# BACKUP_POWER.net
KiCad netlist of a schematic drawn in Altium Designer
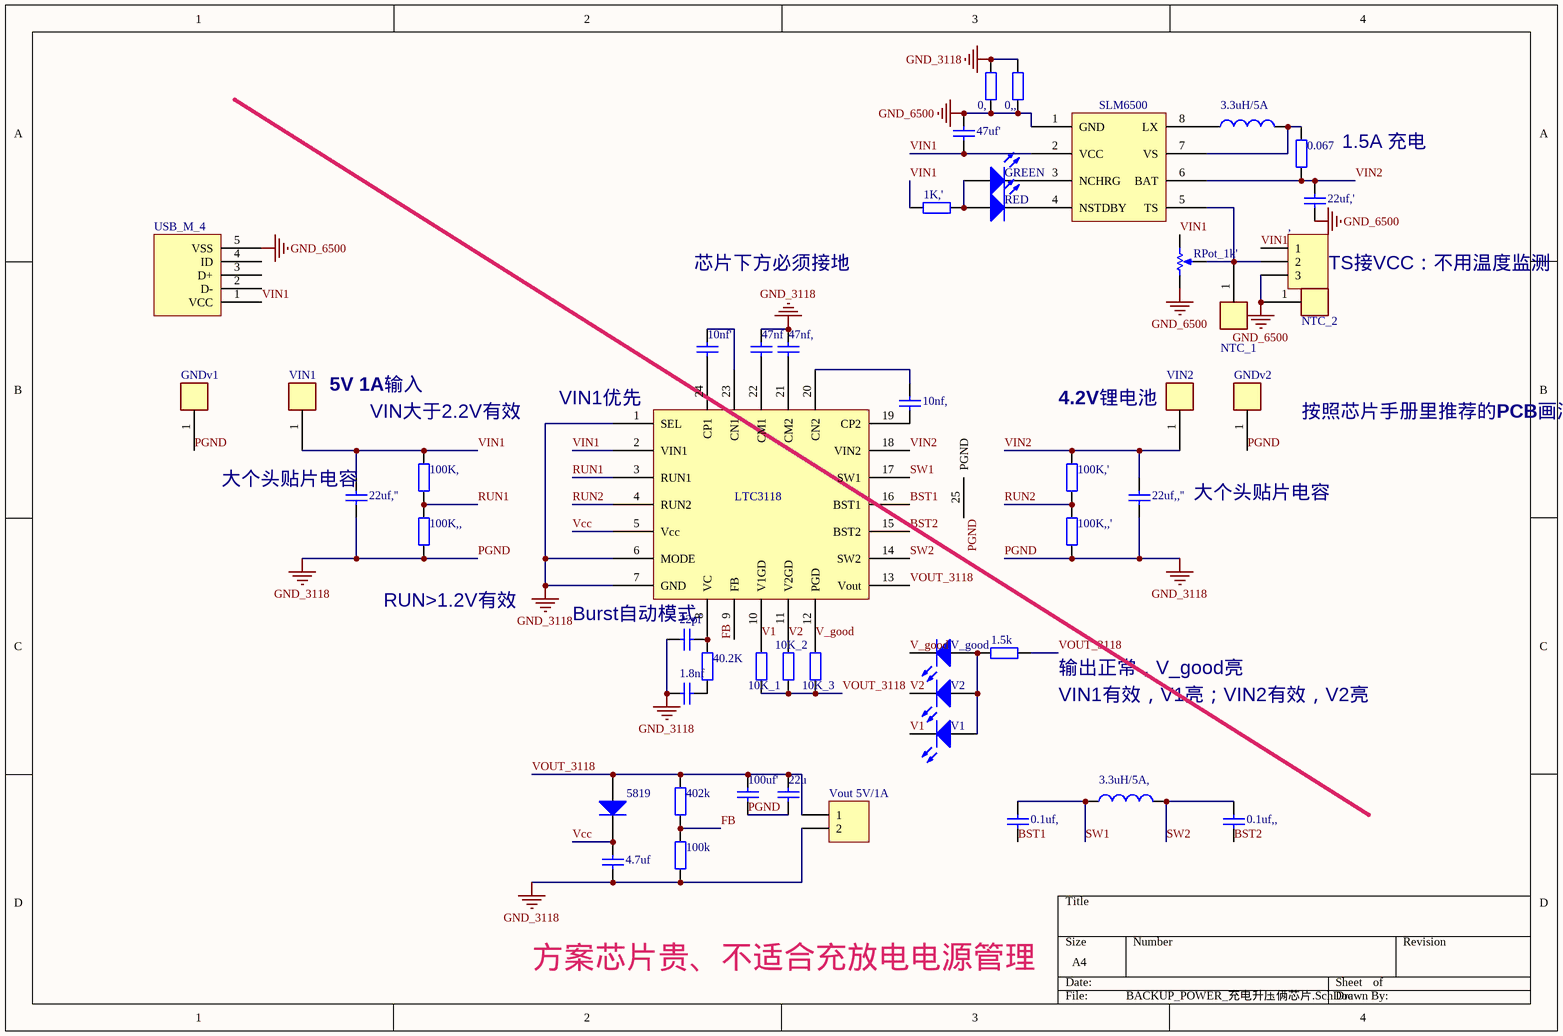
[diagram p0: BACKUP_POWER_充电升压俩芯片.SchDoc]

(export (version "E")
  (design (tool "Eeschema 10.0.6"))
  (components
    (comp (ref ",")
      (value "Header 3")
      (footprint "HDR1X3")
      (description "Header, 3-Pin")
      (fields (field (name "PUBLISHER") "Altium Limited"))
      (libsource (lib "Miscellaneous Connectors") (part "Header 3"))
    )
    (comp (ref "0,")
      (value "Res2")
      (footprint "0805A")
      (description "Resistor")
      (fields (field (name "PUBLISHER") "Altium Limited"))
      (libsource (lib "Miscellaneous Devices") (part "Res2"))
    )
    (comp (ref "0,,")
      (value "Res2")
      (footprint "0805A")
      (description "Resistor")
      (fields (field (name "PUBLISHER") "Altium Limited"))
      (libsource (lib "Miscellaneous Devices") (part "Res2"))
    )
    (comp (ref "0.1uf,")
      (value "Cap")
      (footprint "C-RAD-0805")
      (description "Capacitor")
      (fields (field (name "PUBLISHER") "Altium Limited"))
      (libsource (lib "Miscellaneous Devices") (part "Cap"))
    )
    (comp (ref "0.1uf,,")
      (value "Cap")
      (footprint "C-RAD-0805")
      (description "Capacitor")
      (fields (field (name "PUBLISHER") "Altium Limited"))
      (libsource (lib "Miscellaneous Devices") (part "Cap"))
    )
    (comp (ref "0.067")
      (value "Res2")
      (footprint "1206R")
      (description "Resistor")
      (fields (field (name "PUBLISHER") "Altium Limited"))
      (libsource (lib "Miscellaneous Devices") (part "Res2"))
    )
    (comp (ref "1.5k")
      (value "Res2")
      (footprint "0805A")
      (description "Resistor")
      (fields (field (name "PUBLISHER") "Altium Limited"))
      (libsource (lib "") (part "Res2_1"))
    )
    (comp (ref "1.8nf")
      (value "Cap")
      (footprint "C-RAD-0805")
      (description "Capacitor")
      (fields (field (name "PUBLISHER") "Altium Limited"))
      (libsource (lib "Miscellaneous Devices") (part "Cap"))
    )
    (comp (ref "1K,'")
      (value "Res2")
      (footprint "0805A")
      (description "Resistor")
      (fields (field (name "PUBLISHER") "Altium Limited"))
      (libsource (lib "") (part "Res2_2"))
    )
    (comp (ref "3.3uH/5A")
      (value "Inductor")
      (footprint "6 X 6-L")
      (fields (field (name "PUBLISHER") "Altium Limited"))
      (libsource (lib "Miscellaneous Devices") (part "Inductor"))
    )
    (comp (ref "3.3uH/5A,")
      (value "Inductor")
      (footprint "6 X 6-L")
      (fields (field (name "PUBLISHER") "Altium Limited"))
      (libsource (lib "Miscellaneous Devices") (part "Inductor"))
    )
    (comp (ref "4.7uf")
      (value "Cap")
      (footprint "C-RAD-0805")
      (description "Capacitor")
      (fields (field (name "PUBLISHER") "Altium Limited"))
      (libsource (lib "Miscellaneous Devices") (part "Cap"))
    )
    (comp (ref "10K_1")
      (value "Res2")
      (footprint "0805A")
      (description "Resistor")
      (fields (field (name "PUBLISHER") "Altium Limited"))
      (libsource (lib "Miscellaneous Devices") (part "Res2"))
    )
    (comp (ref "10K_2")
      (value "Res2")
      (footprint "0805A")
      (description "Resistor")
      (fields (field (name "PUBLISHER") "Altium Limited"))
      (libsource (lib "Miscellaneous Devices") (part "Res2"))
    )
    (comp (ref "10K_3")
      (value "Res2")
      (footprint "0805A")
      (description "Resistor")
      (fields (field (name "PUBLISHER") "Altium Limited"))
      (libsource (lib "Miscellaneous Devices") (part "Res2"))
    )
    (comp (ref "10nf'")
      (value "Cap")
      (footprint "C-RAD-0805")
      (description "Capacitor")
      (fields (field (name "PUBLISHER") "Altium Limited"))
      (libsource (lib "Miscellaneous Devices") (part "Cap"))
    )
    (comp (ref "10nf,")
      (value "Cap")
      (footprint "C-RAD-0805")
      (description "Capacitor")
      (fields (field (name "PUBLISHER") "Altium Limited"))
      (libsource (lib "Miscellaneous Devices") (part "Cap"))
    )
    (comp (ref "22pf")
      (value "Cap")
      (footprint "C-RAD-0805")
      (description "Capacitor")
      (fields (field (name "PUBLISHER") "Altium Limited"))
      (libsource (lib "Miscellaneous Devices") (part "Cap"))
    )
    (comp (ref "22u")
      (value "Cap")
      (footprint "MISCEPCB:1812")
      (description "Capacitor")
      (fields (field (name "PUBLISHER") "Altium Limited"))
      (libsource (lib "Miscellaneous Devices") (part "Cap"))
    )
    (comp (ref "22uf,'")
      (value "Cap")
      (footprint "C-RAD-0805")
      (description "Capacitor")
      (fields (field (name "PUBLISHER") "Altium Limited"))
      (libsource (lib "Miscellaneous Devices") (part "Cap"))
    )
    (comp (ref "22uf,''")
      (value "Cap")
      (footprint "MISCEPCB:1812")
      (description "Capacitor")
      (fields (field (name "PUBLISHER") "Altium Limited"))
      (libsource (lib "Miscellaneous Devices") (part "Cap"))
    )
    (comp (ref "22uf,,''")
      (value "Cap")
      (footprint "MISCEPCB:1812")
      (description "Capacitor")
      (fields (field (name "PUBLISHER") "Altium Limited"))
      (libsource (lib "Miscellaneous Devices") (part "Cap"))
    )
    (comp (ref "40.2K")
      (value "Res2")
      (footprint "0805A")
      (description "Resistor")
      (fields (field (name "PUBLISHER") "Altium Limited"))
      (libsource (lib "Miscellaneous Devices") (part "Res2"))
    )
    (comp (ref "47nf")
      (value "Cap")
      (footprint "C-RAD-0805")
      (description "Capacitor")
      (fields (field (name "PUBLISHER") "Altium Limited"))
      (libsource (lib "Miscellaneous Devices") (part "Cap"))
    )
    (comp (ref "47nf,")
      (value "Cap")
      (footprint "C-RAD-0805")
      (description "Capacitor")
      (fields (field (name "PUBLISHER") "Altium Limited"))
      (libsource (lib "Miscellaneous Devices") (part "Cap"))
    )
    (comp (ref "47uf'")
      (value "Cap")
      (footprint "MISCEPCB:1812")
      (description "Capacitor")
      (fields (field (name "PUBLISHER") "Altium Limited"))
      (libsource (lib "Miscellaneous Devices") (part "Cap"))
    )
    (comp (ref "100k")
      (value "Res2")
      (footprint "0805A")
      (description "Resistor")
      (fields (field (name "PUBLISHER") "Altium Limited"))
      (libsource (lib "Miscellaneous Devices") (part "Res2"))
    )
    (comp (ref "100K,")
      (value "Res2")
      (footprint "0805A")
      (description "Resistor")
      (fields (field (name "PUBLISHER") "Altium Limited"))
      (libsource (lib "Miscellaneous Devices") (part "Res2"))
    )
    (comp (ref "100K,'")
      (value "Res2")
      (footprint "0805A")
      (description "Resistor")
      (fields (field (name "PUBLISHER") "Altium Limited"))
      (libsource (lib "Miscellaneous Devices") (part "Res2"))
    )
    (comp (ref "100K,,")
      (value "Res2")
      (footprint "0805A")
      (description "Resistor")
      (fields (field (name "PUBLISHER") "Altium Limited"))
      (libsource (lib "Miscellaneous Devices") (part "Res2"))
    )
    (comp (ref "100K,,'")
      (value "Res2")
      (footprint "0805A")
      (description "Resistor")
      (fields (field (name "PUBLISHER") "Altium Limited"))
      (libsource (lib "Miscellaneous Devices") (part "Res2"))
    )
    (comp (ref "100uf'")
      (value "Cap")
      (footprint "CAP-7343")
      (description "Capacitor")
      (fields (field (name "PUBLISHER") "Altium Limited"))
      (libsource (lib "Miscellaneous Devices") (part "Cap"))
    )
    (comp (ref "402k")
      (value "Res2")
      (footprint "0805A")
      (description "Resistor")
      (fields (field (name "PUBLISHER") "Altium Limited"))
      (libsource (lib "Miscellaneous Devices") (part "Res2"))
    )
    (comp (ref "5819")
      (value "Diode")
      (footprint "DIODE-1206")
      (description "二极管")
      (fields (field (name "PUBLISHER") "Altium Limited"))
      (libsource (lib "Fszhang") (part "Diode"))
    )
    (comp (ref "GNDv1") (value "1PIN") (footprint "PIN1") (libsource (lib "常用器件库_SCH") (part "1PIN")))
    (comp (ref "GNDv2") (value "1PIN") (footprint "PIN1") (libsource (lib "常用器件库_SCH") (part "1PIN")))
    (comp (ref "GREEN")
      (value "LED0")
      (footprint "LED_0805")
      (description "发光二极管")
      (fields (field (name "PUBLISHER") "Altium Limited"))
      (libsource (lib "Fszhang") (part "LED0"))
    )
    (comp (ref "LTC3118") (value "LTC3118 UFD/QFN24") (libsource (lib "LTC3118") (part "LTC3118 UFD/QFN24")))
    (comp (ref "NTC_1") (value "1PIN") (footprint "PIN1") (libsource (lib "") (part "1PIN_1")))
    (comp (ref "NTC_2") (value "1PIN") (footprint "PIN1") (libsource (lib "") (part "1PIN_2")))
    (comp (ref "RED")
      (value "LED0")
      (footprint "LED_0805")
      (description "发光二极管")
      (fields (field (name "PUBLISHER") "Altium Limited"))
      (libsource (lib "Fszhang") (part "LED0"))
    )
    (comp (ref "RPot_1k'")
      (value "RPot")
      (footprint "VR_A1")
      (description "精密可调电阻")
      (fields (field (name "PUBLISHER") "Altium Limited"))
      (libsource (lib "Fszhang") (part "RPot"))
    )
    (comp (ref "SLM6500") (value "SLM6500") (footprint "SOP8") (libsource (lib "LTC3118") (part "SLM6500")))
    (comp (ref "USB_M_4")
      (value "USB_M")
      (footprint "USB_MICRO")
      (description "MicroUSB接口")
      (libsource (lib "Fszhang") (part "USB_M"))
    )
    (comp (ref "V1")
      (value "LED0")
      (footprint "LED_0805")
      (description "发光二极管")
      (fields (field (name "PUBLISHER") "Altium Limited"))
      (libsource (lib "Fszhang") (part "LED0"))
    )
    (comp (ref "V2")
      (value "LED0")
      (footprint "LED_0805")
      (description "发光二极管")
      (fields (field (name "PUBLISHER") "Altium Limited"))
      (libsource (lib "Fszhang") (part "LED0"))
    )
    (comp (ref "VIN1") (value "1PIN") (footprint "PIN1") (libsource (lib "常用器件库_SCH") (part "1PIN")))
    (comp (ref "VIN2") (value "1PIN") (footprint "PIN1") (libsource (lib "常用器件库_SCH") (part "1PIN")))
    (comp (ref "Vout 5V/1A")
      (value "Header 2")
      (footprint "HDR1X2")
      (description "Header, 2-Pin")
      (fields (field (name "PUBLISHER") "Altium Limited"))
      (libsource (lib "Miscellaneous Connectors") (part "Header 2"))
    )
    (comp (ref "V_good")
      (value "LED0")
      (footprint "LED_0805")
      (description "发光二极管")
      (fields (field (name "PUBLISHER") "Altium Limited"))
      (libsource (lib "Fszhang") (part "LED0"))
    )
  )
  (nets
    (net (code "1") (name "/BST1") (class "Default")
      (node (ref "0.1uf,") (pin "1") (pinfunction "1_1") (pintype "passive"))
      (node (ref "LTC3118") (pin "16") (pinfunction "BST1_16") (pintype "passive"))
    )
    (net (code "2") (name "/BST2") (class "Default")
      (node (ref "0.1uf,,") (pin "1") (pinfunction "1_1") (pintype "passive"))
      (node (ref "LTC3118") (pin "15") (pinfunction "BST2_15") (pintype "passive"))
    )
    (net (code "3") (name "/FB") (class "Default")
      (node (ref "100k") (pin "2") (pinfunction "2_2") (pintype "passive"))
      (node (ref "402k") (pin "1") (pinfunction "1_1") (pintype "passive"))
      (node (ref "LTC3118") (pin "9") (pinfunction "FB_9") (pintype "passive"))
    )
    (net (code "4") (name "/RUN1") (class "Default")
      (node (ref "100K,") (pin "1") (pinfunction "1_1") (pintype "passive"))
      (node (ref "100K,,") (pin "2") (pinfunction "2_2") (pintype "passive"))
      (node (ref "LTC3118") (pin "3") (pinfunction "RUN1_3") (pintype "passive"))
    )
    (net (code "5") (name "/RUN2") (class "Default")
      (node (ref "100K,'") (pin "1") (pinfunction "1_1") (pintype "passive"))
      (node (ref "100K,,'") (pin "2") (pinfunction "2_2") (pintype "passive"))
      (node (ref "LTC3118") (pin "4") (pinfunction "RUN2_4") (pintype "passive"))
    )
    (net (code "6") (name "/SW1") (class "Default")
      (node (ref "0.1uf,") (pin "2") (pinfunction "2_2") (pintype "passive"))
      (node (ref "3.3uH/5A,") (pin "1") (pinfunction "1_1") (pintype "passive"))
      (node (ref "LTC3118") (pin "17") (pinfunction "SW1_17") (pintype "passive"))
    )
    (net (code "7") (name "/SW2") (class "Default")
      (node (ref "0.1uf,,") (pin "2") (pinfunction "2_2") (pintype "passive"))
      (node (ref "3.3uH/5A,") (pin "2") (pinfunction "2_2") (pintype "passive"))
      (node (ref "LTC3118") (pin "14") (pinfunction "SW2_14") (pintype "passive"))
    )
    (net (code "8") (name "/V1") (class "Default")
      (node (ref "10K_1") (pin "2") (pinfunction "2_2") (pintype "passive"))
      (node (ref "LTC3118") (pin "10") (pinfunction "V1GD_10") (pintype "passive"))
      (node (ref "V1") (pin "2") (pinfunction "K_2") (pintype "passive"))
    )
    (net (code "9") (name "/V2") (class "Default")
      (node (ref "10K_2") (pin "2") (pinfunction "2_2") (pintype "passive"))
      (node (ref "LTC3118") (pin "11") (pinfunction "V2GD_11") (pintype "passive"))
      (node (ref "V2") (pin "2") (pinfunction "K_2") (pintype "passive"))
    )
    (net (code "10") (name "/VIN1") (class "Default")
      (node (ref ",") (pin "1") (pinfunction "1_1") (pintype "passive"))
      (node (ref "100K,") (pin "2") (pinfunction "2_2") (pintype "passive"))
      (node (ref "1K,'") (pin "1") (pinfunction "1_1") (pintype "passive"))
      (node (ref "22uf,''") (pin "1") (pinfunction "1_1") (pintype "passive"))
      (node (ref "47uf'") (pin "1") (pinfunction "1_1") (pintype "passive"))
      (node (ref "LTC3118") (pin "2") (pinfunction "VIN1_2") (pintype "passive"))
      (node (ref "RPot_1k'") (pin "3") (pinfunction "BOT_3") (pintype "passive"))
      (node (ref "SLM6500") (pin "2") (pinfunction "VCC_2") (pintype "passive"))
      (node (ref "USB_M_4") (pin "1") (pinfunction "VCC_1") (pintype "passive"))
      (node (ref "VIN1") (pin "1") (pintype "passive"))
    )
    (net (code "11") (name "/VIN2") (class "Default")
      (node (ref "0.067") (pin "1") (pinfunction "1_1") (pintype "passive"))
      (node (ref "100K,'") (pin "2") (pinfunction "2_2") (pintype "passive"))
      (node (ref "22uf,'") (pin "2") (pinfunction "2_2") (pintype "passive"))
      (node (ref "22uf,,''") (pin "1") (pinfunction "1_1") (pintype "passive"))
      (node (ref "LTC3118") (pin "18") (pinfunction "VIN2_18") (pintype "passive"))
      (node (ref "SLM6500") (pin "6") (pinfunction "BAT_6") (pintype "passive"))
      (node (ref "VIN2") (pin "1") (pintype "passive"))
    )
    (net (code "12") (name "/VOUT_3118") (class "Default")
      (node (ref "1.5k") (pin "1") (pinfunction "1_1") (pintype "passive"))
      (node (ref "100uf'") (pin "1") (pinfunction "1_1") (pintype "passive"))
      (node (ref "10K_1") (pin "1") (pinfunction "1_1") (pintype "passive"))
      (node (ref "10K_2") (pin "1") (pinfunction "1_1") (pintype "passive"))
      (node (ref "10K_3") (pin "1") (pinfunction "1_1") (pintype "passive"))
      (node (ref "22u") (pin "1") (pinfunction "1_1") (pintype "passive"))
      (node (ref "402k") (pin "2") (pinfunction "2_2") (pintype "passive"))
      (node (ref "5819") (pin "1") (pinfunction "A_1") (pintype "passive"))
      (node (ref "LTC3118") (pin "13") (pinfunction "Vout_13") (pintype "passive"))
      (node (ref "Vout 5V/1A") (pin "1") (pinfunction "1_1") (pintype "passive"))
    )
    (net (code "13") (name "/V_good") (class "Default")
      (node (ref "10K_3") (pin "2") (pinfunction "2_2") (pintype "passive"))
      (node (ref "LTC3118") (pin "12") (pinfunction "PGD_12") (pintype "passive"))
      (node (ref "V_good") (pin "2") (pinfunction "K_2") (pintype "passive"))
    )
    (net (code "14") (name "/Vcc") (class "Default")
      (node (ref "4.7uf") (pin "1") (pinfunction "1_1") (pintype "passive"))
      (node (ref "5819") (pin "2") (pinfunction "K_2") (pintype "passive"))
      (node (ref "LTC3118") (pin "5") (pinfunction "Vcc_5") (pintype "passive"))
    )
    (net (code "15") (name "GND_3118") (class "Default")
      (node (ref "0,") (pin "2") (pinfunction "2_2") (pintype "passive"))
      (node (ref "0,,") (pin "2") (pinfunction "2_2") (pintype "passive"))
      (node (ref "1.8nf") (pin "1") (pinfunction "1_1") (pintype "passive"))
      (node (ref "100K,,") (pin "1") (pinfunction "1_1") (pintype "passive"))
      (node (ref "100K,,'") (pin "1") (pinfunction "1_1") (pintype "passive"))
      (node (ref "100k") (pin "1") (pinfunction "1_1") (pintype "passive"))
      (node (ref "100uf'") (pin "2") (pinfunction "2_2") (pintype "passive"))
      (node (ref "22pf") (pin "1") (pinfunction "1_1") (pintype "passive"))
      (node (ref "22u") (pin "2") (pinfunction "2_2") (pintype "passive"))
      (node (ref "22uf,''") (pin "2") (pinfunction "2_2") (pintype "passive"))
      (node (ref "22uf,,''") (pin "2") (pinfunction "2_2") (pintype "passive"))
      (node (ref "4.7uf") (pin "2") (pinfunction "2_2") (pintype "passive"))
      (node (ref "47nf") (pin "1") (pinfunction "1_1") (pintype "passive"))
      (node (ref "47nf,") (pin "1") (pinfunction "1_1") (pintype "passive"))
      (node (ref "GNDv1") (pin "1") (pintype "passive"))
      (node (ref "GNDv2") (pin "1") (pintype "passive"))
      (node (ref "LTC3118") (pin "1") (pinfunction "SEL_1") (pintype "passive"))
      (node (ref "LTC3118") (pin "25") (pinfunction "PGND_25") (pintype "passive"))
      (node (ref "LTC3118") (pin "6") (pinfunction "MODE_6") (pintype "passive"))
      (node (ref "LTC3118") (pin "7") (pinfunction "GND_7") (pintype "passive"))
      (node (ref "Vout 5V/1A") (pin "2") (pinfunction "2_2") (pintype "passive"))
    )
    (net (code "16") (name "GND_6500") (class "Default")
      (node (ref ",") (pin "3") (pinfunction "3_3") (pintype "passive"))
      (node (ref "0,") (pin "1") (pinfunction "1_1") (pintype "passive"))
      (node (ref "0,,") (pin "1") (pinfunction "1_1") (pintype "passive"))
      (node (ref "22uf,'") (pin "1") (pinfunction "1_1") (pintype "passive"))
      (node (ref "47uf'") (pin "2") (pinfunction "2_2") (pintype "passive"))
      (node (ref "NTC_2") (pin "1") (pintype "passive"))
      (node (ref "RPot_1k'") (pin "1") (pinfunction "TOP_1") (pintype "passive"))
      (node (ref "SLM6500") (pin "1") (pinfunction "GND_1") (pintype "passive"))
      (node (ref "USB_M_4") (pin "5") (pinfunction "VSS_5") (pintype "passive"))
    )
    (net (code "17") (name "Net-(1.8nf-Pad2)") (class "Default")
      (node (ref "1.8nf") (pin "2") (pinfunction "2_2") (pintype "passive"))
      (node (ref "40.2K") (pin "1") (pinfunction "1_1") (pintype "passive"))
    )
    (net (code "18") (name "Net-(GREEN-A)") (class "Default")
      (node (ref "1K,'") (pin "2") (pinfunction "2_2") (pintype "passive"))
      (node (ref "GREEN") (pin "1") (pinfunction "A_1") (pintype "passive"))
      (node (ref "RED") (pin "1") (pinfunction "A_1") (pintype "passive"))
    )
    (net (code "19") (name "Net-(GREEN-K)") (class "Default")
      (node (ref "GREEN") (pin "2") (pinfunction "K_2") (pintype "passive"))
      (node (ref "SLM6500") (pin "3") (pinfunction "NCHRG_3") (pintype "passive"))
    )
    (net (code "20") (name "Net-(LTC3118-CM1)") (class "Default")
      (node (ref "47nf") (pin "2") (pinfunction "2_2") (pintype "passive"))
      (node (ref "LTC3118") (pin "22") (pinfunction "CM1_22") (pintype "passive"))
    )
    (net (code "21") (name "Net-(LTC3118-CM2)") (class "Default")
      (node (ref "47nf,") (pin "2") (pinfunction "2_2") (pintype "passive"))
      (node (ref "LTC3118") (pin "21") (pinfunction "CM2_21") (pintype "passive"))
    )
    (net (code "22") (name "Net-(LTC3118-CN1)") (class "Default")
      (node (ref "10nf'") (pin "1") (pinfunction "1_1") (pintype "passive"))
      (node (ref "LTC3118") (pin "23") (pinfunction "CN1_23") (pintype "passive"))
    )
    (net (code "23") (name "Net-(LTC3118-CN2)") (class "Default")
      (node (ref "10nf,") (pin "2") (pinfunction "2_2") (pintype "passive"))
      (node (ref "LTC3118") (pin "20") (pinfunction "CN2_20") (pintype "passive"))
    )
    (net (code "24") (name "Net-(LTC3118-CP1)") (class "Default")
      (node (ref "10nf'") (pin "2") (pinfunction "2_2") (pintype "passive"))
      (node (ref "LTC3118") (pin "24") (pinfunction "CP1_24") (pintype "passive"))
    )
    (net (code "25") (name "Net-(LTC3118-CP2)") (class "Default")
      (node (ref "10nf,") (pin "1") (pinfunction "1_1") (pintype "passive"))
      (node (ref "LTC3118") (pin "19") (pinfunction "CP2_19") (pintype "passive"))
    )
    (net (code "26") (name "Net-(LTC3118-VC)") (class "Default")
      (node (ref "22pf") (pin "2") (pinfunction "2_2") (pintype "passive"))
      (node (ref "40.2K") (pin "2") (pinfunction "2_2") (pintype "passive"))
      (node (ref "LTC3118") (pin "8") (pinfunction "VC_8") (pintype "passive"))
    )
    (net (code "27") (name "Net-(RED-K)") (class "Default")
      (node (ref "RED") (pin "2") (pinfunction "K_2") (pintype "passive"))
      (node (ref "SLM6500") (pin "4") (pinfunction "NSTDBY_4") (pintype "passive"))
    )
    (net (code "28") (name "Net-(RPot_1k'-TAP)") (class "Default")
      (node (ref ",") (pin "2") (pinfunction "2_2") (pintype "passive"))
      (node (ref "NTC_1") (pin "1") (pintype "passive"))
      (node (ref "RPot_1k'") (pin "2") (pinfunction "TAP_2") (pintype "passive"))
      (node (ref "SLM6500") (pin "5") (pinfunction "TS_5") (pintype "passive"))
    )
    (net (code "29") (name "Net-(SLM6500-LX)") (class "Default")
      (node (ref "3.3uH/5A") (pin "1") (pinfunction "1_1") (pintype "passive"))
      (node (ref "SLM6500") (pin "8") (pinfunction "LX_8") (pintype "passive"))
    )
    (net (code "30") (name "Net-(SLM6500-VS)") (class "Default")
      (node (ref "0.067") (pin "2") (pinfunction "2_2") (pintype "passive"))
      (node (ref "3.3uH/5A") (pin "2") (pinfunction "2_2") (pintype "passive"))
      (node (ref "SLM6500") (pin "7") (pinfunction "VS_7") (pintype "passive"))
    )
    (net (code "31") (name "Net-(V1-A)") (class "Default")
      (node (ref "1.5k") (pin "2") (pinfunction "2_2") (pintype "passive"))
      (node (ref "V1") (pin "1") (pinfunction "A_1") (pintype "passive"))
      (node (ref "V2") (pin "1") (pinfunction "A_1") (pintype "passive"))
      (node (ref "V_good") (pin "1") (pinfunction "A_1") (pintype "passive"))
    )
    (net (code "32") (name "unconnected-(USB_M_4-D+-Pad3)") (class "Default")
      (node (ref "USB_M_4") (pin "3") (pinfunction "D+_3") (pintype "passive"))
    )
    (net (code "33") (name "unconnected-(USB_M_4-D--Pad2)") (class "Default")
      (node (ref "USB_M_4") (pin "2") (pinfunction "D-_2") (pintype "passive"))
    )
    (net (code "34") (name "unconnected-(USB_M_4-ID-Pad4)") (class "Default")
      (node (ref "USB_M_4") (pin "4") (pinfunction "ID_4") (pintype "passive"))
    )
  )
)
